# high_side.net
KiCad netlist of a schematic drawn in EAGLE
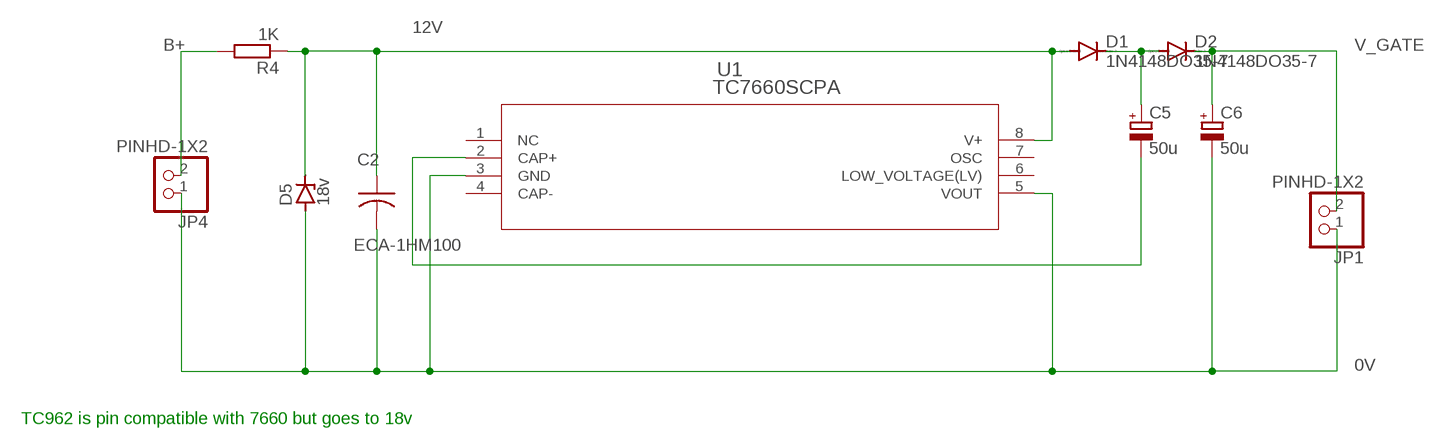
[diagram p0: schematic, sheet 1]

(export (version "E")
  (design (tool "Eeschema 10.0.6"))
  (components
    (comp (ref "C2")
      (value "ECA-1HM100")
      (footprint "eagle-import:CAP_RADIAL_2MM")
      (fields
        (field (name "DIGIKEY_PART_NUMBER") "P5178-ND")
        (field (name "MANUFACTURER") "Panasonic Electronic Components")
        (field (name "CREATED_BY") "PCBLayout.com")
      )
      (libsource (lib "eagle-import") (part "ECA-1HM100"))
    )
    (comp (ref "C5")
      (value "50u")
      (footprint "eagle-import:CAPPRD508W65D1000H1100B")
      (libsource (lib "eagle-import") (part "C-POLRADIAL-11MM-DIA_"))
    )
    (comp (ref "C6")
      (value "50u")
      (footprint "eagle-import:CAPPRD508W65D1000H1100B")
      (libsource (lib "eagle-import") (part "C-POLRADIAL-11MM-DIA_"))
    )
    (comp (ref "D1")
      (value "1N4148DO35-7")
      (footprint "eagle-import:DO35-7")
      (libsource (lib "eagle-import") (part "1N4148DO35-7"))
    )
    (comp (ref "D2")
      (value "1N4148DO35-7")
      (footprint "eagle-import:DO35-7")
      (libsource (lib "eagle-import") (part "1N4148DO35-7"))
    )
    (comp (ref "D5")
      (value "18v")
      (footprint "eagle-import:F126Z10")
      (libsource (lib "eagle-import") (part "ZENER-DIODEF126-10"))
    )
    (comp (ref "JP1")
      (value "PINHD-1X2")
      (footprint "eagle-import:1X02")
      (libsource (lib "eagle-import") (part "PINHD-1X2"))
    )
    (comp (ref "JP4")
      (value "PINHD-1X2")
      (footprint "eagle-import:1X02")
      (libsource (lib "eagle-import") (part "PINHD-1X2"))
    )
    (comp (ref "R4")
      (value "1K")
      (footprint "eagle-import:0204_7")
      (libsource (lib "eagle-import") (part "R-EU_0204/7"))
    )
    (comp (ref "U1")
      (value "TC7660SCPA")
      (footprint "eagle-import:PDIP8_300MC_MCH")
      (fields (field (name "COPYRIGHT") "Copyright (C) 2021 Ultra Librarian. All rights reserved."))
      (libsource (lib "eagle-import") (part "TC7660SCPA"))
    )
  )
  (nets
    (net (code "1") (name "/0V") (class "Default")
      (node (ref "C2") (pin "2") (pinfunction "2_2") (pintype "passive"))
      (node (ref "C6") (pin "2") (pinfunction "-_2") (pintype "passive"))
      (node (ref "D5") (pin "A") (pinfunction "A_A") (pintype "passive"))
      (node (ref "JP1") (pin "1") (pinfunction "1_1") (pintype "passive"))
      (node (ref "JP4") (pin "1") (pinfunction "1_1") (pintype "passive"))
      (node (ref "U1") (pin "3") (pinfunction "GND_3") (pintype "passive"))
      (node (ref "U1") (pin "5") (pinfunction "VOUT_5") (pintype "output"))
    )
    (net (code "2") (name "/12V") (class "Default")
      (node (ref "C2") (pin "1") (pinfunction "1_1") (pintype "passive"))
      (node (ref "D1") (pin "A") (pinfunction "A_A") (pintype "passive"))
      (node (ref "D5") (pin "C") (pinfunction "C_C") (pintype "passive"))
      (node (ref "R4") (pin "1") (pinfunction "1_1") (pintype "passive"))
      (node (ref "U1") (pin "8") (pinfunction "V+_8") (pintype "passive"))
    )
    (net (code "3") (name "/B+") (class "Default")
      (node (ref "JP4") (pin "2") (pinfunction "2_2") (pintype "passive"))
      (node (ref "R4") (pin "2") (pinfunction "2_2") (pintype "passive"))
    )
    (net (code "4") (name "/V_GATE") (class "Default")
      (node (ref "C6") (pin "1") (pinfunction "+_1") (pintype "passive"))
      (node (ref "D2") (pin "C") (pinfunction "C_C") (pintype "passive"))
      (node (ref "JP1") (pin "2") (pinfunction "2_2") (pintype "passive"))
    )
    (net (code "5") (name "Net-(C5-+)") (class "Default")
      (node (ref "C5") (pin "1") (pinfunction "+_1") (pintype "passive"))
      (node (ref "D1") (pin "C") (pinfunction "C_C") (pintype "passive"))
      (node (ref "D2") (pin "A") (pinfunction "A_A") (pintype "passive"))
    )
    (net (code "6") (name "Net-(C5--)") (class "Default")
      (node (ref "C5") (pin "2") (pinfunction "-_2") (pintype "passive"))
      (node (ref "U1") (pin "2") (pinfunction "CAP+_2") (pintype "passive"))
    )
    (net (code "7") (name "unconnected-(U1-CAP--Pad4)") (class "Default")
      (node (ref "U1") (pin "4") (pinfunction "CAP-_4") (pintype "passive"))
    )
    (net (code "8") (name "unconnected-(U1-LOW_VOLTAGE(LV)-Pad6)") (class "Default")
      (node (ref "U1") (pin "6") (pinfunction "LOW_VOLTAGE(LV)_6") (pintype "passive"))
    )
    (net (code "9") (name "unconnected-(U1-NC-Pad1)") (class "Default")
      (node (ref "U1") (pin "1") (pinfunction "NC_1") (pintype "no_connect"))
    )
    (net (code "10") (name "unconnected-(U1-OSC-Pad7)") (class "Default")
      (node (ref "U1") (pin "7") (pinfunction "OSC_7") (pintype "input"))
    )
  )
)
